# Control_IR_Raspberry.net
KiCad netlist of a schematic drawn in Altium Designer
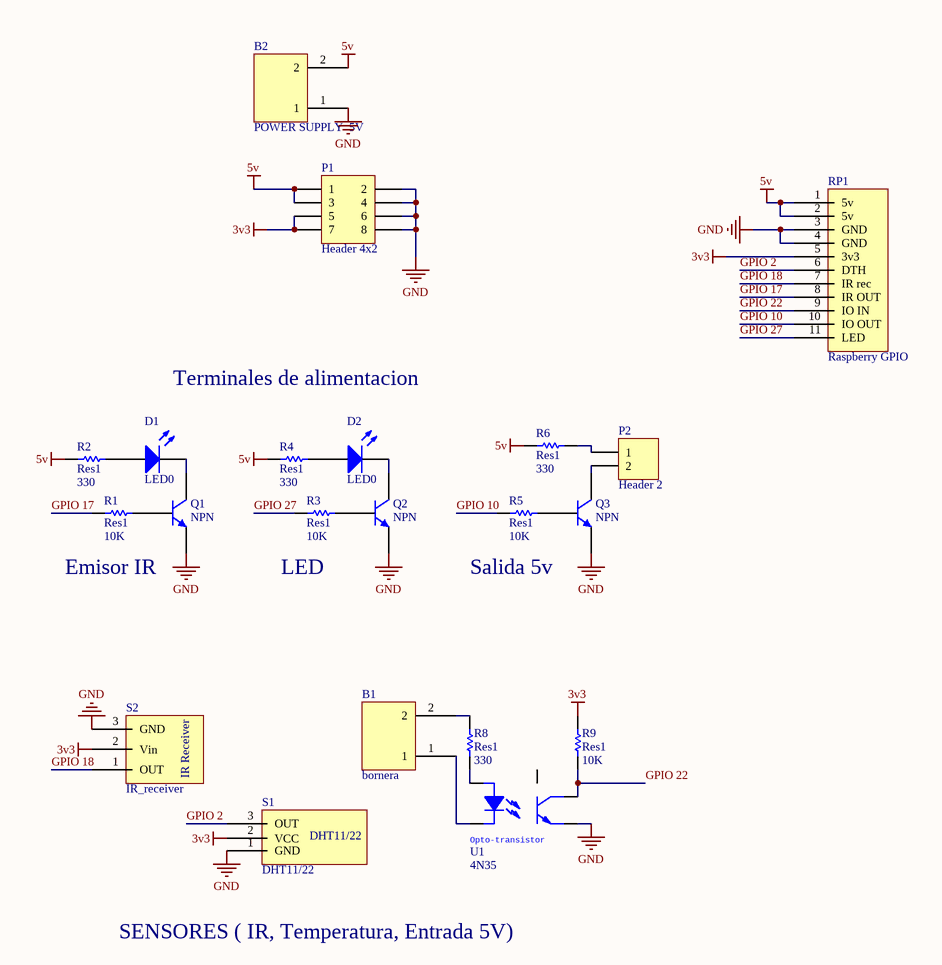
[diagram p0: Control_IR_Raspberry.SchDoc]

(export (version "E")
  (design (tool "Eeschema 10.0.6"))
  (components
    (comp (ref "B1") (value "bornera") (footprint "bornera chica") (libsource (lib "Erick") (part "bornera")))
    (comp (ref "B2")
      (value "POWER SUPPLY  5V")
      (footprint "bornera chica")
      (libsource (lib "Erick") (part "bornera"))
    )
    (comp (ref "D1")
      (value "LED0")
      (footprint "led5mm")
      (description "Typical INFRARED GaAs LED")
      (fields (field (name "PUBLISHER") "Altium Limited"))
      (libsource (lib "Miscellaneous Devices") (part "LED0"))
    )
    (comp (ref "D2")
      (value "LED0")
      (footprint "led5mm")
      (description "Typical INFRARED GaAs LED")
      (fields (field (name "PUBLISHER") "Altium Limited"))
      (libsource (lib "Miscellaneous Devices") (part "LED0"))
    )
    (comp (ref "P1")
      (value "Header 4x2")
      (footprint "Header 4x2")
      (description "Header, 8-Pin, 2-Row")
      (fields (field (name "PUBLISHER") "Altium Limited"))
      (libsource (lib "hphonglib") (part "Header 4x2"))
    )
    (comp (ref "P2")
      (value "Header 2")
      (footprint "Header 2")
      (description "Header, 2-Pin")
      (fields (field (name "PUBLISHER") "Altium Limited"))
      (libsource (lib "hphonglib") (part "Header 2"))
    )
    (comp (ref "Q1")
      (value "NPN")
      (footprint "TO92")
      (description "NPN Bipolar Transistor")
      (fields (field (name "PUBLISHER") "Altium Limited"))
      (libsource (lib "Miscellaneous Devices") (part "NPN"))
    )
    (comp (ref "Q2")
      (value "NPN")
      (footprint "TO92")
      (description "NPN Bipolar Transistor")
      (fields (field (name "PUBLISHER") "Altium Limited"))
      (libsource (lib "Miscellaneous Devices") (part "NPN"))
    )
    (comp (ref "Q3")
      (value "NPN")
      (footprint "TO92")
      (description "NPN Bipolar Transistor")
      (fields (field (name "PUBLISHER") "Altium Limited"))
      (libsource (lib "Miscellaneous Devices") (part "NPN"))
    )
    (comp (ref "R1")
      (value "Res1")
      (footprint "AXIAL-0.3")
      (description "Resistor")
      (fields (field (name "ALTIUM_VALUE") "10K") (field (name "PUBLISHER") "Altium Limited"))
      (libsource (lib "Miscellaneous Devices") (part "Res1"))
    )
    (comp (ref "R2")
      (value "Res1")
      (footprint "AXIAL-0.3")
      (description "Resistor")
      (fields (field (name "ALTIUM_VALUE") "330") (field (name "PUBLISHER") "Altium Limited"))
      (libsource (lib "Miscellaneous Devices") (part "Res1"))
    )
    (comp (ref "R3")
      (value "Res1")
      (footprint "AXIAL-0.3")
      (description "Resistor")
      (fields (field (name "ALTIUM_VALUE") "10K") (field (name "PUBLISHER") "Altium Limited"))
      (libsource (lib "Miscellaneous Devices") (part "Res1"))
    )
    (comp (ref "R4")
      (value "Res1")
      (footprint "AXIAL-0.3")
      (description "Resistor")
      (fields (field (name "ALTIUM_VALUE") "330") (field (name "PUBLISHER") "Altium Limited"))
      (libsource (lib "Miscellaneous Devices") (part "Res1"))
    )
    (comp (ref "R5")
      (value "Res1")
      (footprint "AXIAL-0.3")
      (description "Resistor")
      (fields (field (name "ALTIUM_VALUE") "10K") (field (name "PUBLISHER") "Altium Limited"))
      (libsource (lib "Miscellaneous Devices") (part "Res1"))
    )
    (comp (ref "R6")
      (value "Res1")
      (footprint "AXIAL-0.3")
      (description "Resistor")
      (fields (field (name "ALTIUM_VALUE") "330") (field (name "PUBLISHER") "Altium Limited"))
      (libsource (lib "Miscellaneous Devices") (part "Res1"))
    )
    (comp (ref "R8")
      (value "Res1")
      (footprint "AXIAL-0.3")
      (description "Resistor")
      (fields (field (name "ALTIUM_VALUE") "330") (field (name "PUBLISHER") "Altium Limited"))
      (libsource (lib "Miscellaneous Devices") (part "Res1"))
    )
    (comp (ref "R9")
      (value "Res1")
      (footprint "AXIAL-0.3")
      (description "Resistor")
      (fields (field (name "ALTIUM_VALUE") "10K") (field (name "PUBLISHER") "Altium Limited"))
      (libsource (lib "Miscellaneous Devices") (part "Res1"))
    )
    (comp (ref "RP1")
      (value "Raspberry GPIO")
      (footprint "entradas de placa")
      (libsource (lib "Erick") (part "Raspberry GPIO"))
    )
    (comp (ref "S1") (value "DHT11/22") (footprint "Header 3") (libsource (lib "Erick") (part "DHT11/22")))
    (comp (ref "S2")
      (value "IR_receiver")
      (footprint "Header 3")
      (libsource (lib "Erick") (part "IR_receiver"))
    )
    (comp (ref "U1")
      (value "4N35")
      (footprint "DIP6")
      (description "Opto Couple")
      (fields (field (name "PUBLISHER") "Hoang Nguyen"))
      (libsource (lib "hphonglib") (part "4N35"))
    )
  )
  (nets
    (net (code "1") (name "/GPIO 2") (class "Default")
      (node (ref "RP1") (pin "6") (pinfunction "DTH_6") (pintype "passive"))
      (node (ref "S1") (pin "3") (pinfunction "OUT_3") (pintype "passive"))
    )
    (net (code "2") (name "/GPIO 10") (class "Default")
      (node (ref "R5") (pin "1") (pinfunction "1_1") (pintype "passive"))
      (node (ref "RP1") (pin "10") (pinfunction "IO_OUT_10") (pintype "passive"))
    )
    (net (code "3") (name "/GPIO 17") (class "Default")
      (node (ref "R1") (pin "1") (pinfunction "1_1") (pintype "passive"))
      (node (ref "RP1") (pin "8") (pinfunction "IR_OUT_8") (pintype "passive"))
    )
    (net (code "4") (name "/GPIO 18") (class "Default")
      (node (ref "RP1") (pin "7") (pinfunction "IR_rec_7") (pintype "passive"))
      (node (ref "S2") (pin "1") (pinfunction "OUT_1") (pintype "passive"))
    )
    (net (code "5") (name "/GPIO 22") (class "Default")
      (node (ref "R9") (pin "1") (pinfunction "1_1") (pintype "passive"))
      (node (ref "RP1") (pin "9") (pinfunction "IO_IN_9") (pintype "passive"))
      (node (ref "U1") (pin "5") (pinfunction "5_5") (pintype "passive"))
    )
    (net (code "6") (name "/GPIO 27") (class "Default")
      (node (ref "R3") (pin "1") (pinfunction "1_1") (pintype "passive"))
      (node (ref "RP1") (pin "11") (pinfunction "LED_11") (pintype "passive"))
    )
    (net (code "7") (name "3v3") (class "Default")
      (node (ref "P1") (pin "5") (pinfunction "5_5") (pintype "passive"))
      (node (ref "P1") (pin "7") (pinfunction "7_7") (pintype "passive"))
      (node (ref "R9") (pin "2") (pinfunction "2_2") (pintype "passive"))
      (node (ref "RP1") (pin "5") (pinfunction "3v3_5") (pintype "passive"))
      (node (ref "S1") (pin "2") (pinfunction "VCC_2") (pintype "passive"))
      (node (ref "S2") (pin "2") (pinfunction "Vin_2") (pintype "passive"))
    )
    (net (code "8") (name "5v") (class "Default")
      (node (ref "B2") (pin "2") (pinfunction "2_2") (pintype "passive"))
      (node (ref "P1") (pin "1") (pinfunction "1_1") (pintype "passive"))
      (node (ref "P1") (pin "3") (pinfunction "3_3") (pintype "passive"))
      (node (ref "R2") (pin "1") (pinfunction "1_1") (pintype "passive"))
      (node (ref "R4") (pin "2") (pinfunction "2_2") (pintype "passive"))
      (node (ref "R6") (pin "2") (pinfunction "2_2") (pintype "passive"))
      (node (ref "RP1") (pin "1") (pinfunction "5v_1") (pintype "passive"))
      (node (ref "RP1") (pin "2") (pinfunction "5v_2") (pintype "passive"))
    )
    (net (code "9") (name "GND") (class "Default")
      (node (ref "B2") (pin "1") (pinfunction "1_1") (pintype "passive"))
      (node (ref "P1") (pin "2") (pinfunction "2_2") (pintype "passive"))
      (node (ref "P1") (pin "4") (pinfunction "4_4") (pintype "passive"))
      (node (ref "P1") (pin "6") (pinfunction "6_6") (pintype "passive"))
      (node (ref "P1") (pin "8") (pinfunction "8_8") (pintype "passive"))
      (node (ref "Q1") (pin "3") (pinfunction "E_3") (pintype "passive"))
      (node (ref "Q2") (pin "3") (pinfunction "E_3") (pintype "passive"))
      (node (ref "Q3") (pin "3") (pinfunction "E_3") (pintype "passive"))
      (node (ref "RP1") (pin "3") (pinfunction "GND_3") (pintype "passive"))
      (node (ref "RP1") (pin "4") (pinfunction "GND_4") (pintype "passive"))
      (node (ref "S1") (pin "1") (pinfunction "GND_1") (pintype "passive"))
      (node (ref "S2") (pin "3") (pinfunction "GND_3") (pintype "passive"))
      (node (ref "U1") (pin "4") (pinfunction "4_4") (pintype "passive"))
    )
    (net (code "10") (name "Net-(B1-Pad1)") (class "Default")
      (node (ref "B1") (pin "1") (pinfunction "1_1") (pintype "passive"))
      (node (ref "U1") (pin "2") (pinfunction "2_2") (pintype "passive"))
    )
    (net (code "11") (name "Net-(B1-Pad2)") (class "Default")
      (node (ref "B1") (pin "2") (pinfunction "2_2") (pintype "passive"))
      (node (ref "R8") (pin "2") (pinfunction "2_2") (pintype "passive"))
    )
    (net (code "12") (name "Net-(D1-A)") (class "Default")
      (node (ref "D1") (pin "1") (pinfunction "A_1") (pintype "passive"))
      (node (ref "R2") (pin "2") (pinfunction "2_2") (pintype "passive"))
    )
    (net (code "13") (name "Net-(D1-K)") (class "Default")
      (node (ref "D1") (pin "2") (pinfunction "K_2") (pintype "passive"))
      (node (ref "Q1") (pin "1") (pinfunction "C_1") (pintype "passive"))
    )
    (net (code "14") (name "Net-(D2-A)") (class "Default")
      (node (ref "D2") (pin "1") (pinfunction "A_1") (pintype "passive"))
      (node (ref "R4") (pin "1") (pinfunction "1_1") (pintype "passive"))
    )
    (net (code "15") (name "Net-(D2-K)") (class "Default")
      (node (ref "D2") (pin "2") (pinfunction "K_2") (pintype "passive"))
      (node (ref "Q2") (pin "1") (pinfunction "C_1") (pintype "passive"))
    )
    (net (code "16") (name "Net-(P2-Pad1)") (class "Default")
      (node (ref "P2") (pin "1") (pinfunction "1_1") (pintype "passive"))
      (node (ref "R6") (pin "1") (pinfunction "1_1") (pintype "passive"))
    )
    (net (code "17") (name "Net-(Q1-B)") (class "Default")
      (node (ref "Q1") (pin "2") (pinfunction "B_2") (pintype "passive"))
      (node (ref "R1") (pin "2") (pinfunction "2_2") (pintype "passive"))
    )
    (net (code "18") (name "Net-(Q2-B)") (class "Default")
      (node (ref "Q2") (pin "2") (pinfunction "B_2") (pintype "passive"))
      (node (ref "R3") (pin "2") (pinfunction "2_2") (pintype "passive"))
    )
    (net (code "19") (name "Net-(Q3-B)") (class "Default")
      (node (ref "Q3") (pin "2") (pinfunction "B_2") (pintype "passive"))
      (node (ref "R5") (pin "2") (pinfunction "2_2") (pintype "passive"))
    )
    (net (code "20") (name "Net-(Q3-C)") (class "Default")
      (node (ref "P2") (pin "2") (pinfunction "2_2") (pintype "passive"))
      (node (ref "Q3") (pin "1") (pinfunction "C_1") (pintype "passive"))
    )
    (net (code "21") (name "Net-(R8-Pad1)") (class "Default")
      (node (ref "R8") (pin "1") (pinfunction "1_1") (pintype "passive"))
      (node (ref "U1") (pin "1") (pinfunction "1_1") (pintype "passive"))
    )
    (net (code "22") (name "unconnected-(U1-Pad6)") (class "Default")
      (node (ref "U1") (pin "6") (pinfunction "6_6") (pintype "passive"))
    )
  )
)
